# Sheet1.net
KiCad netlist of a schematic drawn in Altium Designer
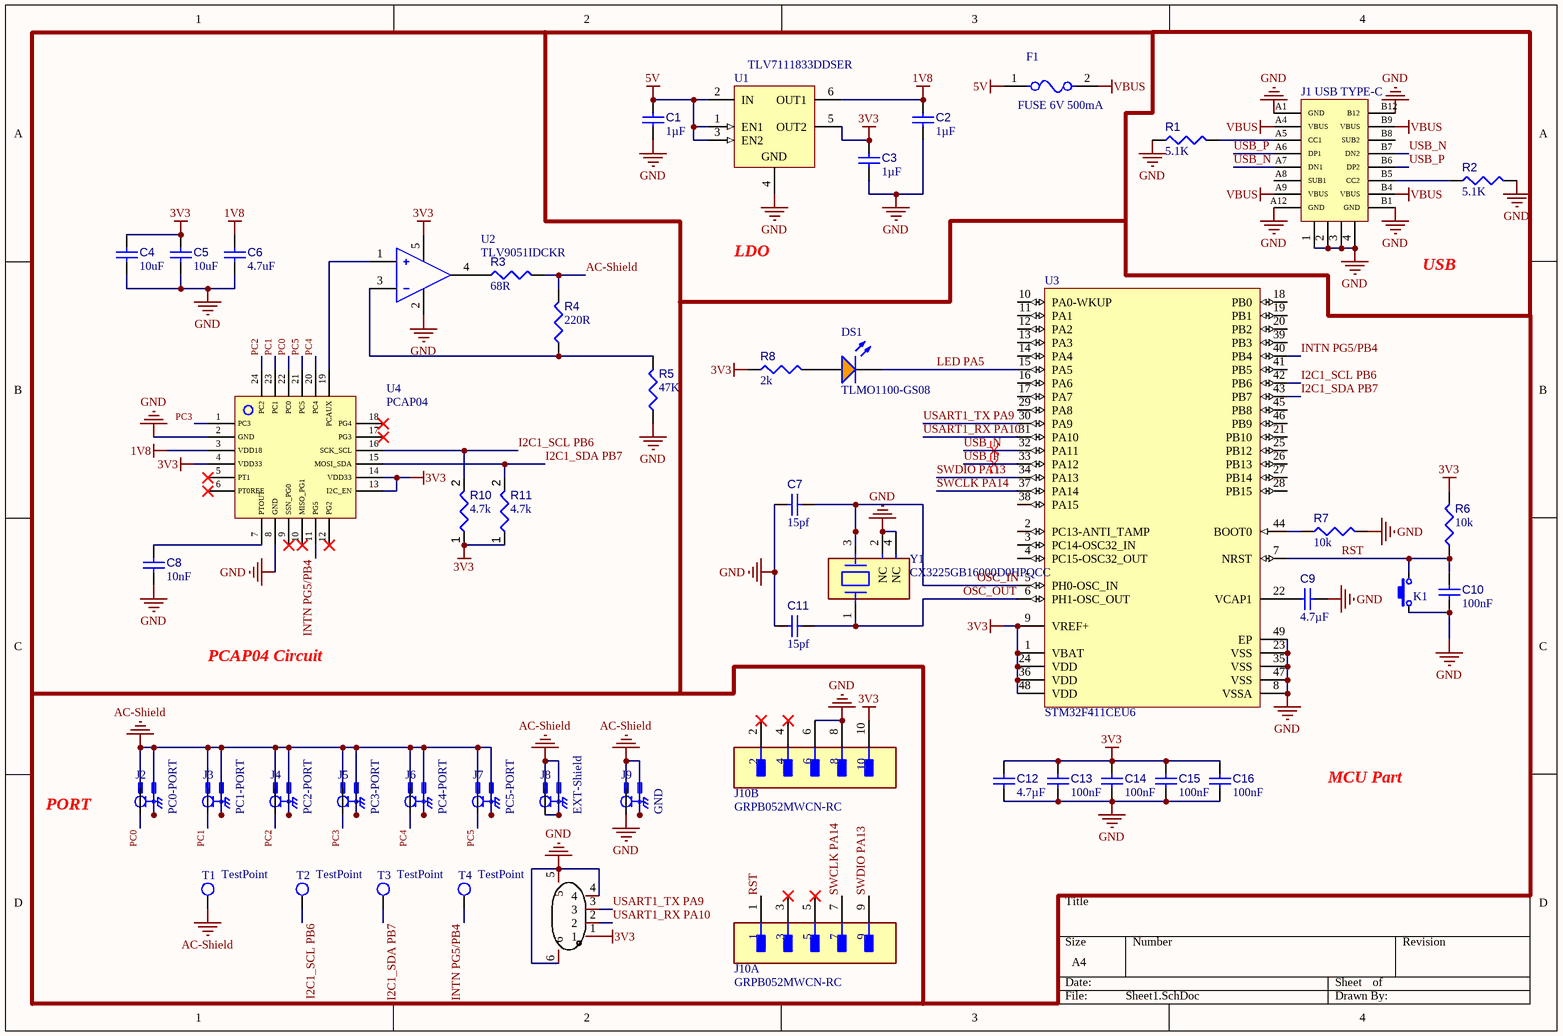
[diagram p0: Sheet1.SchDoc]

(export (version "E")
  (design (tool "Eeschema 10.0.6"))
  (components
    (comp (ref "C1")
      (value "1µF")
      (footprint "CAPC0402(1005)60_L")
      (description "Chip Capacitor, 1µF +/-20%, 10V, 0402, Thickness 0.6 mm")
      (fields (field (name "TOLERANCE") "10%") (field (name "Comment") "Capacitor 1µF +/-20% 10V 0402"))
      (libsource (lib "DigiPCBA Workspace") (part "CAP-NP-2"))
    )
    (comp (ref "C2")
      (value "1µF")
      (footprint "CAPC0402(1005)60_L")
      (description "Chip Capacitor, 1µF +/-20%, 10V, 0402, Thickness 0.6 mm")
      (fields (field (name "TOLERANCE") "10%") (field (name "Comment") "Capacitor 1µF +/-20% 10V 0402"))
      (libsource (lib "DigiPCBA Workspace") (part "CAP-NP-2"))
    )
    (comp (ref "C3")
      (value "1µF")
      (footprint "CAPC0402(1005)60_L")
      (description "Chip Capacitor, 1µF +/-20%, 10V, 0402, Thickness 0.6 mm")
      (fields (field (name "TOLERANCE") "10%") (field (name "Comment") "Capacitor 1µF +/-20% 10V 0402"))
      (libsource (lib "DigiPCBA Workspace") (part "CAP-NP-2"))
    )
    (comp (ref "C4")
      (value "10uF")
      (footprint "CAPC0402(1005)60_L")
      (description "Chip Capacitor, 10µF +/-40%, 6.3V, 0402, Thickness 0.6 mm")
      (fields (field (name "TOLERANCE") "10%") (field (name "Comment") "Capacitor 10µF +/-40% 6.3V 0402"))
      (libsource (lib "DigiPCBA Workspace") (part "CAP-NP-2"))
    )
    (comp (ref "C5")
      (value "10uF")
      (footprint "CAPC0402(1005)60_L")
      (description "Chip Capacitor, 10µF +/-40%, 6.3V, 0402, Thickness 0.6 mm")
      (fields (field (name "TOLERANCE") "10%") (field (name "Comment") "Capacitor 10µF +/-40% 6.3V 0402"))
      (libsource (lib "DigiPCBA Workspace") (part "CAP-NP-2"))
    )
    (comp (ref "C6")
      (value "4.7uF")
      (footprint "CAPC0402(1005)60_L")
      (description "Chip Capacitor, 10µF +/-40%, 6.3V, 0402, Thickness 0.6 mm")
      (fields (field (name "TOLERANCE") "10%") (field (name "Comment") "Capacitor 10µF +/-40% 6.3V 0402"))
      (libsource (lib "DigiPCBA Workspace") (part "CAP-NP-2"))
    )
    (comp (ref "C7")
      (value "15pf")
      (footprint "CAPC0402(1005)60_L")
      (description "Chip Capacitor, 100nF +/-20%, 25V, 0402, Thickness 0.6 mm")
      (fields (field (name "TOLERANCE") "10%") (field (name "Comment") "Capacitor 100nF +/-20% 25V 0402"))
      (libsource (lib "DigiPCBA Workspace") (part "CAP-NP-2"))
    )
    (comp (ref "C8")
      (value "10nF")
      (footprint "CAPC0402(1005)60_L")
      (description "Chip Capacitor, 10nF +/-20%, 50V, 0402, Thickness 0.6 mm")
      (fields (field (name "TOLERANCE") "5%") (field (name "Comment") "Capacitor 10nF +/-20% 50V 0402"))
      (libsource (lib "DigiPCBA Workspace") (part "CAP-NP-2"))
    )
    (comp (ref "C9")
      (value "4.7µF")
      (footprint "CAPC0603(1608)100_L")
      (description "Chip Capacitor, 4.7µF +/-20%, 10V, 0603, Thickness 1 mm")
      (fields (field (name "TOLERANCE") "10%") (field (name "Comment") "Capacitor 4.7µF +/-20% 10V 0603"))
      (libsource (lib "DigiPCBA Workspace") (part "CAP-NP-2"))
    )
    (comp (ref "C10")
      (value "100nF")
      (footprint "CAPC0402(1005)60_L")
      (description "Chip Capacitor, 100nF +/-20%, 25V, 0402, Thickness 0.6 mm")
      (fields (field (name "TOLERANCE") "10%") (field (name "Comment") "Capacitor 100nF +/-20% 25V 0402"))
      (libsource (lib "DigiPCBA Workspace") (part "CAP-NP-2"))
    )
    (comp (ref "C11")
      (value "15pf")
      (footprint "CAPC0402(1005)60_L")
      (description "Chip Capacitor, 100nF +/-20%, 25V, 0402, Thickness 0.6 mm")
      (fields (field (name "TOLERANCE") "10%") (field (name "Comment") "Capacitor 100nF +/-20% 25V 0402"))
      (libsource (lib "DigiPCBA Workspace") (part "CAP-NP-2"))
    )
    (comp (ref "C12")
      (value "4.7µF")
      (footprint "CAPC0603(1608)100_L")
      (description "Chip Capacitor, 4.7µF +/-20%, 10V, 0603, Thickness 1 mm")
      (fields (field (name "TOLERANCE") "10%") (field (name "Comment") "Capacitor 4.7µF +/-20% 10V 0603"))
      (libsource (lib "DigiPCBA Workspace") (part "CAP-NP-2"))
    )
    (comp (ref "C13")
      (value "100nF")
      (footprint "CAPC0402(1005)60_L")
      (description "Chip Capacitor, 100nF +/-20%, 25V, 0402, Thickness 0.6 mm")
      (fields (field (name "TOLERANCE") "10%") (field (name "Comment") "Capacitor 100nF +/-20% 25V 0402"))
      (libsource (lib "DigiPCBA Workspace") (part "CAP-NP-2"))
    )
    (comp (ref "C14")
      (value "100nF")
      (footprint "CAPC0402(1005)60_L")
      (description "Chip Capacitor, 100nF +/-20%, 25V, 0402, Thickness 0.6 mm")
      (fields (field (name "TOLERANCE") "10%") (field (name "Comment") "Capacitor 100nF +/-20% 25V 0402"))
      (libsource (lib "DigiPCBA Workspace") (part "CAP-NP-2"))
    )
    (comp (ref "C15")
      (value "100nF")
      (footprint "CAPC0402(1005)60_L")
      (description "Chip Capacitor, 100nF +/-20%, 25V, 0402, Thickness 0.6 mm")
      (fields (field (name "TOLERANCE") "10%") (field (name "Comment") "Capacitor 100nF +/-20% 25V 0402"))
      (libsource (lib "DigiPCBA Workspace") (part "CAP-NP-2"))
    )
    (comp (ref "C16")
      (value "100nF")
      (footprint "CAPC0402(1005)60_L")
      (description "Chip Capacitor, 100nF +/-20%, 25V, 0402, Thickness 0.6 mm")
      (fields (field (name "TOLERANCE") "10%") (field (name "Comment") "Capacitor 100nF +/-20% 25V 0402"))
      (libsource (lib "DigiPCBA Workspace") (part "CAP-NP-2"))
    )
    (comp (ref "CN1")
      (value "SH1.0-4P")
      (footprint "CONN-SMD_4P-P1.00_WF10004-01200")
      (description "连接器")
      (fields (field (name "MANUFACTURER") "ATOM(爱特姆)") (field (name "MANUFACTURER PART") "WF10004-01200"))
      (libsource (lib "LG_Integrated_Library") (part "SH1.0-4P"))
    )
    (comp (ref "DS1")
      (value "TLMO1100-GS08")
      (footprint "VISH-TLMX1100-2_V")
      (description "Orange LED, 20 mA, 2.1 V, -40 to 100 degC, 2-Pin SMD (0603), RoHS, Tape and Reel")
      (fields (field (name "MANUFACTURER") "Vishay Semiconductor") (field (name "POWER") "90mW"))
      (libsource (lib "DigiPCBA Workspace") (part "LED-ORANGE-AK-2"))
    )
    (comp (ref "F1")
      (value "FUSE 6V 500mA")
      (footprint "FP-0603L-MFG")
      (description "PTC RESET FUSE 15V 100MA 0603")
      (fields
        (field (name "MANUFACTURER PART NUMBER") "0603L010YR")
        (field (name "MANUFACTURER") "Littelfuse Inc")
      )
      (libsource (lib "Altium Content Vault") (part "5bcf9b9f640e542cf0359d10258e979"))
    )
    (comp (ref "J1")
      (value "USB TYPE-C")
      (footprint "TYPE-C-16P")
      (description "USB TYPE-C 母座")
      (libsource (lib "LG_Integrated_Library") (part "USB TYPE-C"))
    )
    (comp (ref "J2")
      (value "PC0-PORT")
      (footprint "LINX_CONMHF4-SMD-G-T")
      (description "IPEX MHF4 Connector Jack, Male Pin 50Ohm Surface Mount Solder")
      (fields (field (name "MP") "CONMHF4-SMD-G-T") (field (name "MF") "Linx Technologies Inc."))
      (libsource (lib "DigiPCBA Workspace") (part "CONMHF4-SMD-G-T"))
    )
    (comp (ref "J3")
      (value "PC1-PORT")
      (footprint "LINX_CONMHF4-SMD-G-T")
      (description "IPEX MHF4 Connector Jack, Male Pin 50Ohm Surface Mount Solder")
      (fields (field (name "MP") "CONMHF4-SMD-G-T") (field (name "MF") "Linx Technologies Inc."))
      (libsource (lib "DigiPCBA Workspace") (part "CONMHF4-SMD-G-T"))
    )
    (comp (ref "J4")
      (value "PC2-PORT")
      (footprint "LINX_CONMHF4-SMD-G-T")
      (description "IPEX MHF4 Connector Jack, Male Pin 50Ohm Surface Mount Solder")
      (fields (field (name "MP") "CONMHF4-SMD-G-T") (field (name "MF") "Linx Technologies Inc."))
      (libsource (lib "DigiPCBA Workspace") (part "CONMHF4-SMD-G-T"))
    )
    (comp (ref "J5")
      (value "PC3-PORT")
      (footprint "LINX_CONMHF4-SMD-G-T")
      (description "IPEX MHF4 Connector Jack, Male Pin 50Ohm Surface Mount Solder")
      (fields (field (name "MP") "CONMHF4-SMD-G-T") (field (name "MF") "Linx Technologies Inc."))
      (libsource (lib "DigiPCBA Workspace") (part "CONMHF4-SMD-G-T"))
    )
    (comp (ref "J6")
      (value "PC4-PORT")
      (footprint "LINX_CONMHF4-SMD-G-T")
      (description "IPEX MHF4 Connector Jack, Male Pin 50Ohm Surface Mount Solder")
      (fields (field (name "MP") "CONMHF4-SMD-G-T") (field (name "MF") "Linx Technologies Inc."))
      (libsource (lib "DigiPCBA Workspace") (part "CONMHF4-SMD-G-T"))
    )
    (comp (ref "J7")
      (value "PC5-PORT")
      (footprint "LINX_CONMHF4-SMD-G-T")
      (description "IPEX MHF4 Connector Jack, Male Pin 50Ohm Surface Mount Solder")
      (fields (field (name "MP") "CONMHF4-SMD-G-T") (field (name "MF") "Linx Technologies Inc."))
      (libsource (lib "DigiPCBA Workspace") (part "CONMHF4-SMD-G-T"))
    )
    (comp (ref "J8")
      (value "EXT-Shield")
      (footprint "LINX_CONMHF4-SMD-G-T")
      (description "IPEX MHF4 Connector Jack, Male Pin 50Ohm Surface Mount Solder")
      (fields (field (name "MP") "CONMHF4-SMD-G-T") (field (name "MF") "Linx Technologies Inc."))
      (libsource (lib "DigiPCBA Workspace") (part "CONMHF4-SMD-G-T"))
    )
    (comp (ref "J9")
      (value "GND")
      (footprint "LINX_CONMHF4-SMD-G-T")
      (description "IPEX MHF4 Connector Jack, Male Pin 50Ohm Surface Mount Solder")
      (fields (field (name "MP") "CONMHF4-SMD-G-T") (field (name "MF") "Linx Technologies Inc."))
      (libsource (lib "DigiPCBA Workspace") (part "CONMHF4-SMD-G-T"))
    )
    (comp (ref "J10")
      (value "GRPB052MWCN-RC")
      (footprint "FP-GRPB052MWCN-RC-MFG")
      (description "CONN HEADER R/A 10POS 1.27MM")
      (fields
        (field (name "OCTOPART") "https://octopart.com/grpb052mwcn-rc-sullins-12268864")
        (field (name "MANUFACTURER") "Sullins")
      )
      (libsource (lib "Altium Content Vault") (part "544f42128f4185dcb88ce1ce9bf1982"))
    )
    (comp (ref "K1")
      (value "Button")
      (footprint "SW-SMD_ST-1185X")
      (libsource (lib "LG_Integrated_Library") (part "Button"))
    )
    (comp (ref "R1")
      (value "5.1K")
      (footprint "RESC0402(1005)_L")
      (description "Chip Resistor, 10 kOhms, +/-1 %, 63 mW, -55 to 125 degC, 0402")
      (fields (field (name "POWER") "63mW") (field (name "TOLERANCE") "1%"))
      (libsource (lib "DigiPCBA Workspace") (part "RES-2"))
    )
    (comp (ref "R2")
      (value "5.1K")
      (footprint "RESC0402(1005)_L")
      (description "Chip Resistor, 10 kOhms, +/-1 %, 63 mW, -55 to 125 degC, 0402")
      (fields (field (name "POWER") "63mW") (field (name "TOLERANCE") "1%"))
      (libsource (lib "DigiPCBA Workspace") (part "RES-2"))
    )
    (comp (ref "R3")
      (value "68R")
      (footprint "RESC0402(1005)_L")
      (description "Chip Resistor, 10 Ohms, +/-1 %, 63 mW, -55 to 155 degC, 0402")
      (fields (field (name "TOLERANCE") "1%") (field (name "POWER") "63mW"))
      (libsource (lib "DigiPCBA Workspace") (part "RES-2"))
    )
    (comp (ref "R4")
      (value "220R")
      (footprint "RESC0402(1005)_L")
      (description "Chip Resistor, 10 Ohms, +/-1 %, 63 mW, -55 to 155 degC, 0402")
      (fields (field (name "TOLERANCE") "1%") (field (name "POWER") "63mW"))
      (libsource (lib "DigiPCBA Workspace") (part "RES-2"))
    )
    (comp (ref "R5")
      (value "47K")
      (footprint "RESC0402(1005)_L")
      (description "Chip Resistor, 10 Ohms, +/-1 %, 63 mW, -55 to 155 degC, 0402")
      (fields (field (name "TOLERANCE") "1%") (field (name "POWER") "63mW"))
      (libsource (lib "DigiPCBA Workspace") (part "RES-2"))
    )
    (comp (ref "R6")
      (value "10k")
      (footprint "RESC0402(1005)_L")
      (description "Chip Resistor, 10 kOhms, +/-1 %, 63 mW, -55 to 125 degC, 0402")
      (fields (field (name "POWER") "63mW") (field (name "TOLERANCE") "1%"))
      (libsource (lib "DigiPCBA Workspace") (part "RES-2"))
    )
    (comp (ref "R7")
      (value "10k")
      (footprint "RESC0402(1005)_L")
      (description "Chip Resistor, 10 kOhms, +/-1 %, 63 mW, -55 to 125 degC, 0402")
      (fields (field (name "POWER") "63mW") (field (name "TOLERANCE") "1%"))
      (libsource (lib "DigiPCBA Workspace") (part "RES-2"))
    )
    (comp (ref "R8")
      (value "2k")
      (footprint "RESC0402(1005)_L")
      (description "Chip Resistor, 10 kOhms, +/-1 %, 63 mW, -55 to 125 degC, 0402")
      (fields (field (name "POWER") "63mW") (field (name "TOLERANCE") "1%"))
      (libsource (lib "DigiPCBA Workspace") (part "RES-2"))
    )
    (comp (ref "R10")
      (value "4.7k")
      (footprint "RESC0402(1005)_L")
      (description "Chip Resistor, 4,7 kOhms, +/-1 %, 63 mW, -55 to 155 degC, 0402")
      (fields (field (name "POWER") "63mW") (field (name "TOLERANCE") "1%"))
      (libsource (lib "") (part "RES-2_1"))
    )
    (comp (ref "R11")
      (value "4.7k")
      (footprint "RESC0402(1005)_L")
      (description "Chip Resistor, 4,7 kOhms, +/-1 %, 63 mW, -55 to 155 degC, 0402")
      (fields (field (name "POWER") "63mW") (field (name "TOLERANCE") "1%"))
      (libsource (lib "") (part "RES-2_1"))
    )
    (comp (ref "T1")
      (value "TestPoint")
      (footprint "TestPoint")
      (libsource (lib "LG_Integrated_Library") (part "TestPoint"))
    )
    (comp (ref "T2")
      (value "TestPoint")
      (footprint "TestPoint")
      (libsource (lib "LG_Integrated_Library") (part "TestPoint"))
    )
    (comp (ref "T3")
      (value "TestPoint")
      (footprint "TestPoint")
      (libsource (lib "LG_Integrated_Library") (part "TestPoint"))
    )
    (comp (ref "T4")
      (value "TestPoint")
      (footprint "TestPoint")
      (libsource (lib "LG_Integrated_Library") (part "TestPoint"))
    )
    (comp (ref "U1")
      (value "TLV7111833DDSER")
      (footprint "DSE0006A_V")
      (fields (field (name "MANUFACTURER") "Texas Instruments"))
      (libsource (lib "Altium Content Vault") (part "TI-TLV71XXXXX-DSE6"))
    )
    (comp (ref "U2")
      (value "TLV9051IDCKR")
      (footprint "FP-DCK0005A-IPC_A")
      (description "IC OPAMP GP 1 CIRCUIT SC70-5")
      (libsource (lib "Altium Content Vault") (part "d26da39eff9d56ed2cb7351b5ff93ab"))
    )
    (comp (ref "U3")
      (value "STM32F411CEU6")
      (footprint "STM-UFQFPN48_N")
      (libsource (lib "Altium Content Vault") (part "MC-ARM-STM32F411-UFQFPN48"))
    )
    (comp (ref "U4")
      (value "PCAP04")
      (footprint "QFN-24-PAD")
      (description "CDC IC")
      (libsource (lib "LG_Integrated_Library") (part "PCAP04"))
    )
    (comp (ref "Y1")
      (value "CX3225GB16000D0HPQCC")
      (footprint "FP-CX3225GB-MFG")
      (description "CRYSTAL 16.0000MHZ 8PF SMD")
      (fields (field (name "TOLERANCE") "20ppm"))
      (libsource (lib "Altium Content Vault") (part "485821f88a3d0e4767168cc8d80ed41"))
    )
  )
  (nets
    (net (code "1") (name "/I2C1_SCL PB6") (class "Default")
      (node (ref "R10") (pin "2") (pinfunction "2_2") (pintype "passive"))
      (node (ref "T2") (pin "1") (pinfunction "1_1") (pintype "passive"))
      (node (ref "U3") (pin "42") (pinfunction "PB6_42") (pintype "bidirectional"))
      (node (ref "U4") (pin "16") (pinfunction "SCK_SCL_16") (pintype "passive"))
    )
    (net (code "2") (name "/I2C1_SDA PB7") (class "Default")
      (node (ref "R11") (pin "2") (pinfunction "2_2") (pintype "passive"))
      (node (ref "T3") (pin "1") (pinfunction "1_1") (pintype "passive"))
      (node (ref "U3") (pin "43") (pinfunction "PB7_43") (pintype "bidirectional"))
      (node (ref "U4") (pin "15") (pinfunction "MOSI_SDA_15") (pintype "passive"))
    )
    (net (code "3") (name "/INTN PG5{slash}PB4") (class "Default")
      (node (ref "T4") (pin "1") (pinfunction "1_1") (pintype "passive"))
      (node (ref "U3") (pin "40") (pinfunction "PB4_40") (pintype "bidirectional"))
      (node (ref "U4") (pin "11") (pinfunction "PG5_11") (pintype "passive"))
    )
    (net (code "4") (name "/LED PA5") (class "Default")
      (node (ref "DS1") (pin "2") (pinfunction "K_2") (pintype "passive"))
      (node (ref "U3") (pin "15") (pinfunction "PA5_15") (pintype "bidirectional"))
    )
    (net (code "5") (name "/OSC_IN") (class "Default")
      (node (ref "C7") (pin "1") (pinfunction "1_1") (pintype "passive"))
      (node (ref "U3") (pin "5") (pinfunction "PH0-OSC_IN_5") (pintype "bidirectional"))
      (node (ref "Y1") (pin "3") (pinfunction "2_HOT_3") (pintype "passive"))
    )
    (net (code "6") (name "/OSC_OUT") (class "Default")
      (node (ref "C11") (pin "1") (pinfunction "1_1") (pintype "passive"))
      (node (ref "U3") (pin "6") (pinfunction "PH1-OSC_OUT_6") (pintype "bidirectional"))
      (node (ref "Y1") (pin "1") (pinfunction "1_HOT_1") (pintype "passive"))
    )
    (net (code "7") (name "/PC0") (class "Default")
      (node (ref "J2") (pin "1") (pinfunction "1_1") (pintype "passive"))
      (node (ref "U4") (pin "22") (pinfunction "PC0_22") (pintype "passive"))
    )
    (net (code "8") (name "/PC1") (class "Default")
      (node (ref "J3") (pin "1") (pinfunction "1_1") (pintype "passive"))
      (node (ref "U4") (pin "23") (pinfunction "PC1_23") (pintype "passive"))
    )
    (net (code "9") (name "/PC2") (class "Default")
      (node (ref "J4") (pin "1") (pinfunction "1_1") (pintype "passive"))
      (node (ref "U4") (pin "24") (pinfunction "PC2_24") (pintype "passive"))
    )
    (net (code "10") (name "/PC3") (class "Default")
      (node (ref "J5") (pin "1") (pinfunction "1_1") (pintype "passive"))
      (node (ref "U4") (pin "1") (pinfunction "PC3_1") (pintype "passive"))
    )
    (net (code "11") (name "/PC4") (class "Default")
      (node (ref "J6") (pin "1") (pinfunction "1_1") (pintype "passive"))
      (node (ref "U4") (pin "20") (pinfunction "PC4_20") (pintype "passive"))
    )
    (net (code "12") (name "/PC5") (class "Default")
      (node (ref "J7") (pin "1") (pinfunction "1_1") (pintype "passive"))
      (node (ref "U4") (pin "21") (pinfunction "PC5_21") (pintype "passive"))
    )
    (net (code "13") (name "/RST") (class "Default")
      (node (ref "C10") (pin "2") (pinfunction "2_2") (pintype "passive"))
      (node (ref "J10") (pin "1") (pinfunction "1_1") (pintype "passive"))
      (node (ref "K1") (pin "2") (pinfunction "2_2") (pintype "passive"))
      (node (ref "R6") (pin "1") (pinfunction "1_1") (pintype "passive"))
      (node (ref "U3") (pin "7") (pinfunction "NRST_7") (pintype "bidirectional"))
    )
    (net (code "14") (name "/SWCLK PA14") (class "Default")
      (node (ref "J10") (pin "7") (pinfunction "7_7") (pintype "passive"))
      (node (ref "U3") (pin "37") (pinfunction "PA14_37") (pintype "bidirectional"))
    )
    (net (code "15") (name "/SWDIO PA13") (class "Default")
      (node (ref "J10") (pin "9") (pinfunction "9_9") (pintype "passive"))
      (node (ref "U3") (pin "34") (pinfunction "PA13_34") (pintype "bidirectional"))
    )
    (net (code "16") (name "/USART1_RX PA10") (class "Default")
      (node (ref "CN1") (pin "2") (pinfunction "2_2") (pintype "passive"))
      (node (ref "U3") (pin "31") (pinfunction "PA10_31") (pintype "bidirectional"))
    )
    (net (code "17") (name "/USART1_TX PA9") (class "Default")
      (node (ref "CN1") (pin "3") (pinfunction "3_3") (pintype "passive"))
      (node (ref "U3") (pin "30") (pinfunction "PA9_30") (pintype "bidirectional"))
    )
    (net (code "18") (name "/USB_N") (class "Default")
      (node (ref "J1") (pin "A7") (pinfunction "DN1_A7") (pintype "passive"))
      (node (ref "J1") (pin "B7") (pinfunction "DN2_B7") (pintype "passive"))
      (node (ref "U3") (pin "32") (pinfunction "PA11_32") (pintype "bidirectional"))
    )
    (net (code "19") (name "/USB_P") (class "Default")
      (node (ref "J1") (pin "A6") (pinfunction "DP1_A6") (pintype "passive"))
      (node (ref "J1") (pin "B6") (pinfunction "DP2_B6") (pintype "passive"))
      (node (ref "U3") (pin "33") (pinfunction "PA12_33") (pintype "bidirectional"))
    )
    (net (code "20") (name "1V8") (class "Default")
      (node (ref "C2") (pin "1") (pinfunction "1_1") (pintype "passive"))
      (node (ref "C6") (pin "2") (pinfunction "2_2") (pintype "passive"))
      (node (ref "U1") (pin "6") (pinfunction "OUT1_6") (pintype "power_in"))
      (node (ref "U4") (pin "3") (pinfunction "VDD18_3") (pintype "passive"))
    )
    (net (code "21") (name "3V3") (class "Default")
      (node (ref "C12") (pin "2") (pinfunction "2_2") (pintype "passive"))
      (node (ref "C13") (pin "2") (pinfunction "2_2") (pintype "passive"))
      (node (ref "C14") (pin "2") (pinfunction "2_2") (pintype "passive"))
      (node (ref "C15") (pin "2") (pinfunction "2_2") (pintype "passive"))
      (node (ref "C16") (pin "2") (pinfunction "2_2") (pintype "passive"))
      (node (ref "C3") (pin "1") (pinfunction "1_1") (pintype "passive"))
      (node (ref "C4") (pin "2") (pinfunction "2_2") (pintype "passive"))
      (node (ref "C5") (pin "2") (pinfunction "2_2") (pintype "passive"))
      (node (ref "CN1") (pin "1") (pinfunction "1_1") (pintype "passive"))
      (node (ref "J10") (pin "10") (pinfunction "10_10") (pintype "passive"))
      (node (ref "R10") (pin "1") (pinfunction "1_1") (pintype "passive"))
      (node (ref "R11") (pin "1") (pinfunction "1_1") (pintype "passive"))
      (node (ref "R6") (pin "2") (pinfunction "2_2") (pintype "passive"))
      (node (ref "R8") (pin "1") (pinfunction "1_1") (pintype "passive"))
      (node (ref "U1") (pin "5") (pinfunction "OUT2_5") (pintype "power_in"))
      (node (ref "U2") (pin "5") (pinfunction "V+_5") (pintype "power_in"))
      (node (ref "U3") (pin "1") (pinfunction "VBAT_1") (pintype "power_in"))
      (node (ref "U3") (pin "24") (pinfunction "VDD_24") (pintype "power_in"))
      (node (ref "U3") (pin "36") (pinfunction "VDD_36") (pintype "power_in"))
      (node (ref "U3") (pin "48") (pinfunction "VDD_48") (pintype "power_in"))
      (node (ref "U3") (pin "9") (pinfunction "VREF+_9") (pintype "power_in"))
      (node (ref "U4") (pin "13") (pinfunction "I2C_EN_13") (pintype "passive"))
      (node (ref "U4") (pin "14") (pinfunction "VDD33_14") (pintype "passive"))
      (node (ref "U4") (pin "4") (pinfunction "VDD33_4") (pintype "passive"))
    )
    (net (code "22") (name "5V") (class "Default")
      (node (ref "C1") (pin "1") (pinfunction "1_1") (pintype "passive"))
      (node (ref "F1") (pin "1") (pinfunction "1_1") (pintype "passive"))
      (node (ref "U1") (pin "1") (pinfunction "EN1_1") (pintype "input"))
      (node (ref "U1") (pin "2") (pinfunction "IN_2") (pintype "power_in"))
      (node (ref "U1") (pin "3") (pinfunction "EN2_3") (pintype "input"))
    )
    (net (code "23") (name "AC-Shield") (class "Default")
      (node (ref "J2") (pin "S1") (pinfunction "2_S1") (pintype "passive"))
      (node (ref "J2") (pin "S2") (pinfunction "2_S2") (pintype "passive"))
      (node (ref "J2") (pin "S3") (pinfunction "2_S3") (pintype "passive"))
      (node (ref "J3") (pin "S1") (pinfunction "2_S1") (pintype "passive"))
      (node (ref "J3") (pin "S2") (pinfunction "2_S2") (pintype "passive"))
      (node (ref "J3") (pin "S3") (pinfunction "2_S3") (pintype "passive"))
      (node (ref "J4") (pin "S1") (pinfunction "2_S1") (pintype "passive"))
      (node (ref "J4") (pin "S2") (pinfunction "2_S2") (pintype "passive"))
      (node (ref "J4") (pin "S3") (pinfunction "2_S3") (pintype "passive"))
      (node (ref "J5") (pin "S1") (pinfunction "2_S1") (pintype "passive"))
      (node (ref "J5") (pin "S2") (pinfunction "2_S2") (pintype "passive"))
      (node (ref "J5") (pin "S3") (pinfunction "2_S3") (pintype "passive"))
      (node (ref "J6") (pin "S1") (pinfunction "2_S1") (pintype "passive"))
      (node (ref "J6") (pin "S2") (pinfunction "2_S2") (pintype "passive"))
      (node (ref "J6") (pin "S3") (pinfunction "2_S3") (pintype "passive"))
      (node (ref "J7") (pin "S1") (pinfunction "2_S1") (pintype "passive"))
      (node (ref "J7") (pin "S2") (pinfunction "2_S2") (pintype "passive"))
      (node (ref "J7") (pin "S3") (pinfunction "2_S3") (pintype "passive"))
      (node (ref "J8") (pin "1") (pinfunction "1_1") (pintype "passive"))
      (node (ref "J8") (pin "S1") (pinfunction "2_S1") (pintype "passive"))
      (node (ref "J8") (pin "S2") (pinfunction "2_S2") (pintype "passive"))
      (node (ref "J8") (pin "S3") (pinfunction "2_S3") (pintype "passive"))
      (node (ref "J9") (pin "S1") (pinfunction "2_S1") (pintype "passive"))
      (node (ref "J9") (pin "S2") (pinfunction "2_S2") (pintype "passive"))
      (node (ref "J9") (pin "S3") (pinfunction "2_S3") (pintype "passive"))
      (node (ref "R3") (pin "2") (pinfunction "2_2") (pintype "passive"))
      (node (ref "R4") (pin "2") (pinfunction "2_2") (pintype "passive"))
      (node (ref "T1") (pin "1") (pinfunction "1_1") (pintype "passive"))
    )
    (net (code "24") (name "GND") (class "Default")
      (node (ref "C1") (pin "2") (pinfunction "2_2") (pintype "passive"))
      (node (ref "C10") (pin "1") (pinfunction "1_1") (pintype "passive"))
      (node (ref "C11") (pin "2") (pinfunction "2_2") (pintype "passive"))
      (node (ref "C12") (pin "1") (pinfunction "1_1") (pintype "passive"))
      (node (ref "C13") (pin "1") (pinfunction "1_1") (pintype "passive"))
      (node (ref "C14") (pin "1") (pinfunction "1_1") (pintype "passive"))
      (node (ref "C15") (pin "1") (pinfunction "1_1") (pintype "passive"))
      (node (ref "C16") (pin "1") (pinfunction "1_1") (pintype "passive"))
      (node (ref "C2") (pin "2") (pinfunction "2_2") (pintype "passive"))
      (node (ref "C3") (pin "2") (pinfunction "2_2") (pintype "passive"))
      (node (ref "C4") (pin "1") (pinfunction "1_1") (pintype "passive"))
      (node (ref "C5") (pin "1") (pinfunction "1_1") (pintype "passive"))
      (node (ref "C6") (pin "1") (pinfunction "1_1") (pintype "passive"))
      (node (ref "C7") (pin "2") (pinfunction "2_2") (pintype "passive"))
      (node (ref "C8") (pin "1") (pinfunction "1_1") (pintype "passive"))
      (node (ref "C9") (pin "2") (pinfunction "2_2") (pintype "passive"))
      (node (ref "CN1") (pin "4") (pinfunction "4_4") (pintype "passive"))
      (node (ref "CN1") (pin "5") (pinfunction "5_5") (pintype "passive"))
      (node (ref "CN1") (pin "6") (pinfunction "6_6") (pintype "passive"))
      (node (ref "J1") (pin "1") (pinfunction "9_1") (pintype "passive"))
      (node (ref "J1") (pin "2") (pinfunction "10_2") (pintype "passive"))
      (node (ref "J1") (pin "3") (pinfunction "11_3") (pintype "passive"))
      (node (ref "J1") (pin "4") (pinfunction "12_4") (pintype "passive"))
      (node (ref "J1") (pin "A1") (pinfunction "GND_A1") (pintype "passive"))
      (node (ref "J1") (pin "A12") (pinfunction "GND_A12") (pintype "passive"))
      (node (ref "J1") (pin "B1") (pinfunction "GND_B1") (pintype "passive"))
      (node (ref "J1") (pin "B12") (pinfunction "B12_B12") (pintype "passive"))
      (node (ref "J10") (pin "6") (pinfunction "6_6") (pintype "passive"))
      (node (ref "J10") (pin "8") (pinfunction "8_8") (pintype "passive"))
      (node (ref "J9") (pin "1") (pinfunction "1_1") (pintype "passive"))
      (node (ref "K1") (pin "1") (pinfunction "1_1") (pintype "passive"))
      (node (ref "R1") (pin "1") (pinfunction "1_1") (pintype "passive"))
      (node (ref "R2") (pin "2") (pinfunction "2_2") (pintype "passive"))
      (node (ref "R5") (pin "1") (pinfunction "1_1") (pintype "passive"))
      (node (ref "R7") (pin "2") (pinfunction "2_2") (pintype "passive"))
      (node (ref "U1") (pin "4") (pinfunction "GND_4") (pintype "power_in"))
      (node (ref "U2") (pin "2") (pinfunction "V-_2") (pintype "power_in"))
      (node (ref "U3") (pin "23") (pinfunction "VSS_23") (pintype "power_in"))
      (node (ref "U3") (pin "35") (pinfunction "VSS_35") (pintype "power_in"))
      (node (ref "U3") (pin "47") (pinfunction "VSS_47") (pintype "power_in"))
      (node (ref "U3") (pin "49") (pinfunction "EP_49") (pintype "power_in"))
      (node (ref "U3") (pin "8") (pinfunction "VSSA_8") (pintype "power_in"))
      (node (ref "U4") (pin "2") (pinfunction "GND_2") (pintype "passive"))
      (node (ref "U4") (pin "8") (pinfunction "GND_8") (pintype "passive"))
      (node (ref "Y1") (pin "2") (pinfunction "NC_2") (pintype "passive"))
      (node (ref "Y1") (pin "4") (pinfunction "NC_4") (pintype "passive"))
    )
    (net (code "25") (name "Net-(DS1-A)") (class "Default")
      (node (ref "DS1") (pin "1") (pinfunction "A_1") (pintype "passive"))
      (node (ref "R8") (pin "2") (pinfunction "2_2") (pintype "passive"))
    )
    (net (code "26") (name "Net-(J1-CC1)") (class "Default")
      (node (ref "J1") (pin "A5") (pinfunction "CC1_A5") (pintype "passive"))
      (node (ref "R1") (pin "2") (pinfunction "2_2") (pintype "passive"))
    )
    (net (code "27") (name "Net-(J1-CC2)") (class "Default")
      (node (ref "J1") (pin "B5") (pinfunction "CC2_B5") (pintype "passive"))
      (node (ref "R2") (pin "1") (pinfunction "1_1") (pintype "passive"))
    )
    (net (code "28") (name "Net-(U2-IN+)") (class "Default")
      (node (ref "U2") (pin "1") (pinfunction "IN+_1") (pintype "tri_state"))
      (node (ref "U4") (pin "19") (pinfunction "PCAUX_19") (pintype "passive"))
    )
    (net (code "29") (name "Net-(U2-IN-)") (class "Default")
      (node (ref "R4") (pin "1") (pinfunction "1_1") (pintype "passive"))
      (node (ref "R5") (pin "2") (pinfunction "2_2") (pintype "passive"))
      (node (ref "U2") (pin "3") (pinfunction "IN-_3") (pintype "tri_state"))
    )
    (net (code "30") (name "Net-(U2-OUT)") (class "Default")
      (node (ref "R3") (pin "1") (pinfunction "1_1") (pintype "passive"))
      (node (ref "U2") (pin "4") (pinfunction "OUT_4") (pintype "passive"))
    )
    (net (code "31") (name "Net-(U3-BOOT0)") (class "Default")
      (node (ref "R7") (pin "1") (pinfunction "1_1") (pintype "passive"))
      (node (ref "U3") (pin "44") (pinfunction "BOOT0_44") (pintype "input"))
    )
    (net (code "32") (name "Net-(U3-VCAP1)") (class "Default")
      (node (ref "C9") (pin "1") (pinfunction "1_1") (pintype "passive"))
      (node (ref "U3") (pin "22") (pinfunction "VCAP1_22") (pintype "passive"))
    )
    (net (code "33") (name "Net-(U4-PTOUT)") (class "Default")
      (node (ref "C8") (pin "2") (pinfunction "2_2") (pintype "passive"))
      (node (ref "U4") (pin "7") (pinfunction "PTOUT_7") (pintype "passive"))
    )
    (net (code "34") (name "VBUS") (class "Default")
      (node (ref "F1") (pin "2") (pinfunction "2_2") (pintype "passive"))
      (node (ref "J1") (pin "A4") (pinfunction "VBUS_A4") (pintype "passive"))
      (node (ref "J1") (pin "A9") (pinfunction "VBUS_A9") (pintype "passive"))
      (node (ref "J1") (pin "B4") (pinfunction "VBUS_B4") (pintype "passive"))
      (node (ref "J1") (pin "B9") (pinfunction "VBUS_B9") (pintype "passive"))
    )
    (net (code "35") (name "unconnected-(J1-SUB1-PadA8)") (class "Default")
      (node (ref "J1") (pin "A8") (pinfunction "SUB1_A8") (pintype "passive"))
    )
    (net (code "36") (name "unconnected-(J1-SUB2-PadB8)") (class "Default")
      (node (ref "J1") (pin "B8") (pinfunction "SUB2_B8") (pintype "passive"))
    )
    (net (code "37") (name "unconnected-(J10-Pad2)") (class "Default")
      (node (ref "J10") (pin "2") (pinfunction "2_2") (pintype "passive+no_connect"))
    )
    (net (code "38") (name "unconnected-(J10-Pad3)") (class "Default")
      (node (ref "J10") (pin "3") (pinfunction "3_3") (pintype "passive+no_connect"))
    )
    (net (code "39") (name "unconnected-(J10-Pad4)") (class "Default")
      (node (ref "J10") (pin "4") (pinfunction "4_4") (pintype "passive+no_connect"))
    )
    (net (code "40") (name "unconnected-(J10-Pad5)") (class "Default")
      (node (ref "J10") (pin "5") (pinfunction "5_5") (pintype "passive+no_connect"))
    )
    (net (code "41") (name "unconnected-(U3-PA0-WKUP-Pad10)") (class "Default")
      (node (ref "U3") (pin "10") (pinfunction "PA0-WKUP_10") (pintype "bidirectional"))
    )
    (net (code "42") (name "unconnected-(U3-PA1-Pad11)") (class "Default")
      (node (ref "U3") (pin "11") (pinfunction "PA1_11") (pintype "bidirectional"))
    )
    (net (code "43") (name "unconnected-(U3-PA2-Pad12)") (class "Default")
      (node (ref "U3") (pin "12") (pinfunction "PA2_12") (pintype "bidirectional"))
    )
    (net (code "44") (name "unconnected-(U3-PA3-Pad13)") (class "Default")
      (node (ref "U3") (pin "13") (pinfunction "PA3_13") (pintype "bidirectional"))
    )
    (net (code "45") (name "unconnected-(U3-PA4-Pad14)") (class "Default")
      (node (ref "U3") (pin "14") (pinfunction "PA4_14") (pintype "bidirectional"))
    )
    (net (code "46") (name "unconnected-(U3-PA6-Pad16)") (class "Default")
      (node (ref "U3") (pin "16") (pinfunction "PA6_16") (pintype "bidirectional"))
    )
    (net (code "47") (name "unconnected-(U3-PA7-Pad17)") (class "Default")
      (node (ref "U3") (pin "17") (pinfunction "PA7_17") (pintype "bidirectional"))
    )
    (net (code "48") (name "unconnected-(U3-PA8-Pad29)") (class "Default")
      (node (ref "U3") (pin "29") (pinfunction "PA8_29") (pintype "bidirectional"))
    )
    (net (code "49") (name "unconnected-(U3-PA15-Pad38)") (class "Default")
      (node (ref "U3") (pin "38") (pinfunction "PA15_38") (pintype "bidirectional"))
    )
    (net (code "50") (name "unconnected-(U3-PB0-Pad18)") (class "Default")
      (node (ref "U3") (pin "18") (pinfunction "PB0_18") (pintype "bidirectional"))
    )
    (net (code "51") (name "unconnected-(U3-PB1-Pad19)") (class "Default")
      (node (ref "U3") (pin "19") (pinfunction "PB1_19") (pintype "bidirectional"))
    )
    (net (code "52") (name "unconnected-(U3-PB2-Pad20)") (class "Default")
      (node (ref "U3") (pin "20") (pinfunction "PB2_20") (pintype "bidirectional"))
    )
    (net (code "53") (name "unconnected-(U3-PB3-Pad39)") (class "Default")
      (node (ref "U3") (pin "39") (pinfunction "PB3_39") (pintype "bidirectional"))
    )
    (net (code "54") (name "unconnected-(U3-PB5-Pad41)") (class "Default")
      (node (ref "U3") (pin "41") (pinfunction "PB5_41") (pintype "bidirectional"))
    )
    (net (code "55") (name "unconnected-(U3-PB8-Pad45)") (class "Default")
      (node (ref "U3") (pin "45") (pinfunction "PB8_45") (pintype "bidirectional"))
    )
    (net (code "56") (name "unconnected-(U3-PB9-Pad46)") (class "Default")
      (node (ref "U3") (pin "46") (pinfunction "PB9_46") (pintype "bidirectional"))
    )
    (net (code "57") (name "unconnected-(U3-PB10-Pad21)") (class "Default")
      (node (ref "U3") (pin "21") (pinfunction "PB10_21") (pintype "bidirectional"))
    )
    (net (code "58") (name "unconnected-(U3-PB12-Pad25)") (class "Default")
      (node (ref "U3") (pin "25") (pinfunction "PB12_25") (pintype "bidirectional"))
    )
    (net (code "59") (name "unconnected-(U3-PB13-Pad26)") (class "Default")
      (node (ref "U3") (pin "26") (pinfunction "PB13_26") (pintype "bidirectional"))
    )
    (net (code "60") (name "unconnected-(U3-PB14-Pad27)") (class "Default")
      (node (ref "U3") (pin "27") (pinfunction "PB14_27") (pintype "bidirectional"))
    )
    (net (code "61") (name "unconnected-(U3-PB15-Pad28)") (class "Default")
      (node (ref "U3") (pin "28") (pinfunction "PB15_28") (pintype "bidirectional"))
    )
    (net (code "62") (name "unconnected-(U3-PC13-ANTI_TAMP-Pad2)") (class "Default")
      (node (ref "U3") (pin "2") (pinfunction "PC13-ANTI_TAMP_2") (pintype "bidirectional"))
    )
    (net (code "63") (name "unconnected-(U3-PC14-OSC32_IN-Pad3)") (class "Default")
      (node (ref "U3") (pin "3") (pinfunction "PC14-OSC32_IN_3") (pintype "bidirectional"))
    )
    (net (code "64") (name "unconnected-(U3-PC15-OSC32_OUT-Pad4)") (class "Default")
      (node (ref "U3") (pin "4") (pinfunction "PC15-OSC32_OUT_4") (pintype "bidirectional"))
    )
    (net (code "65") (name "unconnected-(U4-MISO_PG1-Pad10)") (class "Default")
      (node (ref "U4") (pin "10") (pinfunction "MISO_PG1_10") (pintype "passive+no_connect"))
    )
    (net (code "66") (name "unconnected-(U4-PG2-Pad12)") (class "Default")
      (node (ref "U4") (pin "12") (pinfunction "PG2_12") (pintype "passive+no_connect"))
    )
    (net (code "67") (name "unconnected-(U4-PG3-Pad17)") (class "Default")
      (node (ref "U4") (pin "17") (pinfunction "PG3_17") (pintype "passive+no_connect"))
    )
    (net (code "68") (name "unconnected-(U4-PG4-Pad18)") (class "Default")
      (node (ref "U4") (pin "18") (pinfunction "PG4_18") (pintype "passive+no_connect"))
    )
    (net (code "69") (name "unconnected-(U4-PT0REF-Pad6)") (class "Default")
      (node (ref "U4") (pin "6") (pinfunction "PT0REF_6") (pintype "passive+no_connect"))
    )
    (net (code "70") (name "unconnected-(U4-PT1-Pad5)") (class "Default")
      (node (ref "U4") (pin "5") (pinfunction "PT1_5") (pintype "passive+no_connect"))
    )
    (net (code "71") (name "unconnected-(U4-SSN_PG0-Pad9)") (class "Default")
      (node (ref "U4") (pin "9") (pinfunction "SSN_PG0_9") (pintype "passive+no_connect"))
    )
  )
)
